# BV100011_ControlPower.net
KiCad netlist of a schematic drawn in Altium Designer
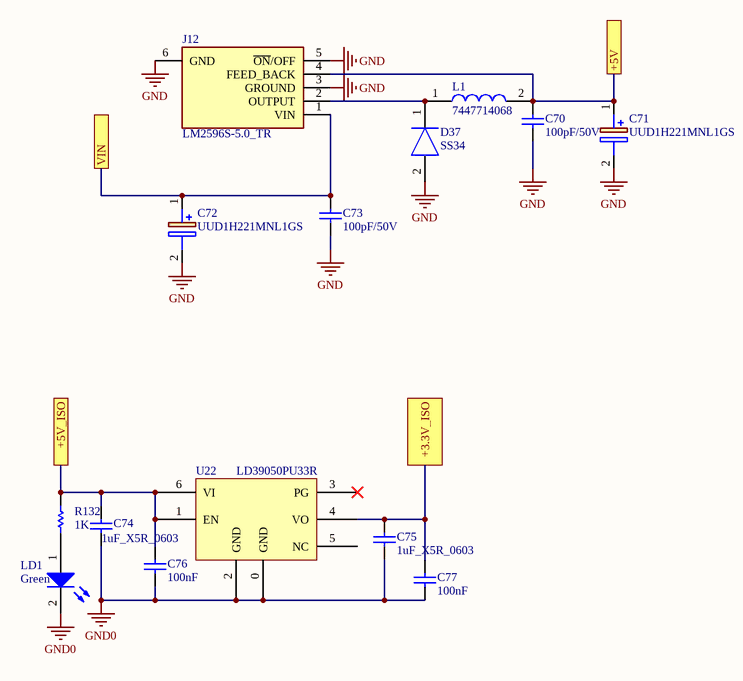
[diagram p0: BV100011_ControlPower.SchDoc]

(export (version "E")
  (design (tool "Eeschema 10.0.6"))
  (components
    (comp (ref "C70")
      (value "100pF/50V")
      (footprint "C1210")
      (description "Capacitor (Semiconductor SIM Model)")
      (fields (field (name "PUBLISHER") "Altium Limited"))
      (libsource (lib "Miscellaneous Devices") (part "Cap Semi"))
    )
    (comp (ref "C71")
      (value "UUD1H221MNL1GS")
      (footprint "SamacSys:CAPAE1030X1050N")
      (description "Capacitor Polarised")
      (fields (field (name "MOUSER PART NUMBER") "647-UUD1H221MNL"))
      (libsource (lib "*") (part "UUD1H221MNL1GS"))
    )
    (comp (ref "C72")
      (value "UUD1H221MNL1GS")
      (footprint "SamacSys:CAPAE1030X1050N")
      (description "Capacitor Polarised")
      (fields (field (name "MOUSER PART NUMBER") "647-UUD1H221MNL"))
      (libsource (lib "*") (part "UUD1H221MNL1GS"))
    )
    (comp (ref "C73")
      (value "100pF/50V")
      (footprint "C1210")
      (description "Capacitor (Semiconductor SIM Model)")
      (fields (field (name "PUBLISHER") "Altium Limited"))
      (libsource (lib "Miscellaneous Devices") (part "Cap Semi"))
    )
    (comp (ref "C74")
      (value "1uF_X5R_0603")
      (footprint "0603C")
      (description "0603  X5R 1µF")
      (fields (field (name "TOLERANCE") "10%"))
      (libsource (lib "MB963_1") (part "CAP SMD 0603  X5R 1µF 25V 10%"))
    )
    (comp (ref "C75")
      (value "1uF_X5R_0603")
      (footprint "0603C")
      (description "0603  X5R 1µF")
      (fields (field (name "TOLERANCE") "10%"))
      (libsource (lib "MB963_1") (part "CAP SMD 0603  X5R 1µF 25V 10%"))
    )
    (comp (ref "C76")
      (value "100nF")
      (footprint "0603C")
      (description "Capacitor 0402 / 0603 / 0805")
      (libsource (lib "MCD_TOOLS") (part "Capacitor_ST"))
    )
    (comp (ref "C77")
      (value "100nF")
      (footprint "0603C")
      (description "Capacitor 0402 / 0603 / 0805")
      (libsource (lib "MCD_TOOLS") (part "Capacitor_ST"))
    )
    (comp (ref "D37")
      (value "SS34")
      (footprint "SamacSys:DIOM6959X262N")
      (description "Diode")
      (libsource (lib "*") (part "SS34"))
    )
    (comp (ref "J12")
      (value "LM2596S-5.0_TR")
      (footprint "SamacSys:LM2596S50TR")
      (description "Connector")
      (fields (field (name "MANUFACTURER_PART_NUMBER") "LM2596S-5.0/TR"))
      (libsource (lib "*") (part "LM2596S-5.0_TR"))
    )
    (comp (ref "L1")
      (value "7447714068")
      (footprint "SamacSys:WE-PD_1030/105054")
      (description "Inductor")
      (fields (field (name "MOUSER PART NUMBER") "710-7447714068"))
      (libsource (lib "*") (part "7447714068"))
    )
    (comp (ref "LD1")
      (value "Green")
      (footprint "0603D-G")
      (description "Typical RED, GREEN, YELLOW, AMBER GaAs LED")
      (fields (field (name "PUBLISHER") "Altium Limited"))
      (libsource (lib "Miscellaneous Devices") (part "LED2"))
    )
    (comp (ref "R132")
      (value "1K")
      (footprint "0603R")
      (description "Resistor 0402 / 0603 / 0805")
      (libsource (lib "MCD_TOOLS") (part "Resistor_ST"))
    )
    (comp (ref "U22")
      (value "LD39050PU33R")
      (footprint "DFN6_0R95_3x3_TP")
      (libsource (lib "MB1137") (part "LD39050P"))
    )
  )
  (nets
    (net (code "1") (name "/+3.3V_ISO") (class "Default")
      (node (ref "C75") (pin "1") (pinfunction "1_1") (pintype "passive"))
      (node (ref "C77") (pin "2") (pinfunction "2_2") (pintype "passive"))
      (node (ref "U22") (pin "4") (pinfunction "VO_4") (pintype "passive"))
    )
    (net (code "2") (name "/+5V") (class "Default")
      (node (ref "C70") (pin "2") (pinfunction "2_2") (pintype "passive"))
      (node (ref "C71") (pin "1") (pinfunction "+_1") (pintype "passive"))
      (node (ref "J12") (pin "4") (pinfunction "FEED_BACK_4") (pintype "passive"))
      (node (ref "L1") (pin "2") (pinfunction "2_2") (pintype "passive"))
    )
    (net (code "3") (name "/+5V_ISO") (class "Default")
      (node (ref "C74") (pin "1") (pinfunction "1_1") (pintype "passive"))
      (node (ref "C76") (pin "2") (pinfunction "2_2") (pintype "passive"))
      (node (ref "R132") (pin "2") (pinfunction "2_2") (pintype "passive"))
      (node (ref "U22") (pin "1") (pinfunction "EN_1") (pintype "passive"))
      (node (ref "U22") (pin "6") (pinfunction "VI_6") (pintype "passive"))
    )
    (net (code "4") (name "/VIN") (class "Default")
      (node (ref "C72") (pin "1") (pinfunction "+_1") (pintype "passive"))
      (node (ref "C73") (pin "2") (pinfunction "2_2") (pintype "passive"))
      (node (ref "J12") (pin "1") (pinfunction "VIN_1") (pintype "passive"))
    )
    (net (code "5") (name "GND") (class "Default")
      (node (ref "C70") (pin "1") (pinfunction "1_1") (pintype "passive"))
      (node (ref "C71") (pin "2") (pinfunction "-_2") (pintype "passive"))
      (node (ref "C72") (pin "2") (pinfunction "-_2") (pintype "passive"))
      (node (ref "C73") (pin "1") (pinfunction "1_1") (pintype "passive"))
      (node (ref "D37") (pin "2") (pinfunction "A_2") (pintype "passive"))
      (node (ref "J12") (pin "3") (pinfunction "GROUND_3") (pintype "passive"))
      (node (ref "J12") (pin "5") (pinfunction "~{ON}/OFF_5") (pintype "passive"))
      (node (ref "J12") (pin "6") (pinfunction "GND_6") (pintype "passive"))
    )
    (net (code "6") (name "GND0") (class "Default")
      (node (ref "C74") (pin "2") (pinfunction "2_2") (pintype "passive"))
      (node (ref "C75") (pin "2") (pinfunction "2_2") (pintype "passive"))
      (node (ref "C76") (pin "1") (pinfunction "1_1") (pintype "passive"))
      (node (ref "C77") (pin "1") (pinfunction "1_1") (pintype "passive"))
      (node (ref "LD1") (pin "2") (pinfunction "K_2") (pintype "passive"))
      (node (ref "U22") (pin "0") (pinfunction "GND_0") (pintype "passive"))
      (node (ref "U22") (pin "2") (pinfunction "GND_2") (pintype "passive"))
    )
    (net (code "7") (name "Net-(D37-K)") (class "Default")
      (node (ref "D37") (pin "1") (pinfunction "K_1") (pintype "passive"))
      (node (ref "J12") (pin "2") (pinfunction "OUTPUT_2") (pintype "passive"))
      (node (ref "L1") (pin "1") (pinfunction "1_1") (pintype "passive"))
    )
    (net (code "8") (name "Net-(LD1-A)") (class "Default")
      (node (ref "LD1") (pin "1") (pinfunction "A_1") (pintype "passive"))
      (node (ref "R132") (pin "1") (pinfunction "1_1") (pintype "passive"))
    )
    (net (code "9") (name "unconnected-(U22-NC-Pad5)") (class "Default")
      (node (ref "U22") (pin "5") (pinfunction "NC_5") (pintype "passive"))
    )
    (net (code "10") (name "unconnected-(U22-PG-Pad3)") (class "Default")
      (node (ref "U22") (pin "3") (pinfunction "PG_3") (pintype "passive+no_connect"))
    )
  )
)
